# BUCK.net
KiCad netlist of a schematic drawn in Altium Designer
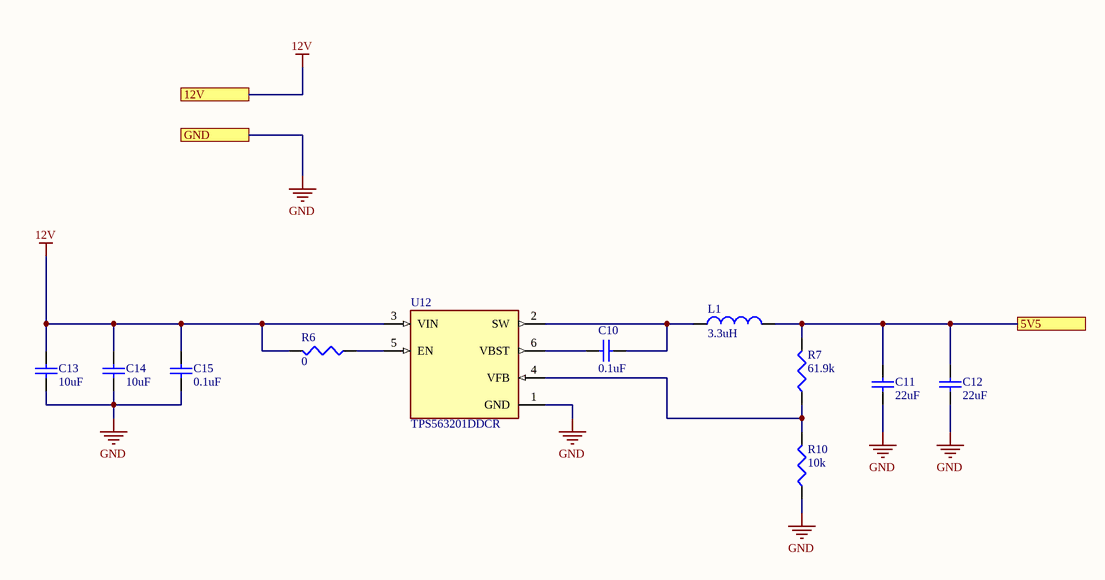
[diagram p0: BUCK.SchDoc]

(export (version "E")
  (design (tool "Eeschema 10.0.6"))
  (components
    (comp (ref "C10")
      (value "0.1uF")
      (footprint "SMD-0603")
      (description "Ceramic Capacitor 0603")
      (libsource (lib "LCR") (part "CAP0603"))
    )
    (comp (ref "C11")
      (value "22uF")
      (footprint "SMD-0805")
      (description "Ceramic Capacitor 0805 Imperial (2012 Metric)")
      (libsource (lib "LCR") (part "CAP0805"))
    )
    (comp (ref "C12")
      (value "22uF")
      (footprint "SMD-0805")
      (description "Ceramic Capacitor 0805 Imperial (2012 Metric)")
      (libsource (lib "LCR") (part "CAP0805"))
    )
    (comp (ref "C13")
      (value "10uF")
      (footprint "SMD-1206")
      (description "Ceramic Capacitor 1206 Imperial, 25V")
      (libsource (lib "LCR") (part "CAP1206_HV"))
    )
    (comp (ref "C14")
      (value "10uF")
      (footprint "SMD-1206")
      (description "Ceramic Capacitor 1206 Imperial, 25V")
      (libsource (lib "LCR") (part "CAP1206_HV"))
    )
    (comp (ref "C15")
      (value "0.1uF")
      (footprint "SMD-0603")
      (description "Ceramic Capacitor 0603, 25V")
      (libsource (lib "LCR") (part "CAP0603_HV"))
    )
    (comp (ref "L1")
      (value "3.3uH")
      (footprint "SMD-2525")
      (description "VLS6045EX type Inductor 2525")
      (libsource (lib "LCR") (part "VLS6045EX"))
    )
    (comp (ref "R6")
      (value "0")
      (footprint "SMD-0603")
      (description "Resistor-0603")
      (libsource (lib "LCR") (part "RES0603"))
    )
    (comp (ref "R7")
      (value "61.9k")
      (footprint "SMD-0603")
      (description "Resistor-0603")
      (libsource (lib "LCR") (part "RES0603"))
    )
    (comp (ref "R10")
      (value "10k")
      (footprint "SMD-0603")
      (description "Resistor-0603")
      (libsource (lib "LCR") (part "RES0603"))
    )
    (comp (ref "U12")
      (value "TPS563201DDCR")
      (footprint "SOT95P280X110-6N")
      (description "4.5 V to 17 V input, 3 A output, synchronous step-down converter in Eco-mode")
      (fields (field (name "MF") "Texas Instruments"))
      (libsource (lib "PowerManagement") (part "TPS563201DDCR"))
    )
  )
  (nets
    (net (code "1") (name "/5V5") (class "Default")
      (node (ref "C11") (pin "2") (pinfunction "2_2") (pintype "passive"))
      (node (ref "C12") (pin "2") (pinfunction "2_2") (pintype "passive"))
      (node (ref "L1") (pin "2") (pinfunction "2_2") (pintype "passive"))
      (node (ref "R7") (pin "2") (pinfunction "2_2") (pintype "passive"))
    )
    (net (code "2") (name "12V") (class "Default")
      (node (ref "C13") (pin "2") (pinfunction "2_2") (pintype "passive"))
      (node (ref "C14") (pin "2") (pinfunction "2_2") (pintype "passive"))
      (node (ref "C15") (pin "2") (pinfunction "2_2") (pintype "passive"))
      (node (ref "R6") (pin "2") (pinfunction "2_2") (pintype "passive"))
      (node (ref "U12") (pin "3") (pinfunction "VIN_3") (pintype "input"))
    )
    (net (code "3") (name "GND") (class "Default")
      (node (ref "C11") (pin "1") (pinfunction "1_1") (pintype "passive"))
      (node (ref "C12") (pin "1") (pinfunction "1_1") (pintype "passive"))
      (node (ref "C13") (pin "1") (pinfunction "1_1") (pintype "passive"))
      (node (ref "C14") (pin "1") (pinfunction "1_1") (pintype "passive"))
      (node (ref "C15") (pin "1") (pinfunction "1_1") (pintype "passive"))
      (node (ref "R10") (pin "1") (pinfunction "1_1") (pintype "passive"))
      (node (ref "U12") (pin "1") (pinfunction "GND_1") (pintype "power_in"))
    )
    (net (code "4") (name "Net-(U12-EN)") (class "Default")
      (node (ref "R6") (pin "1") (pinfunction "1_1") (pintype "passive"))
      (node (ref "U12") (pin "5") (pinfunction "EN_5") (pintype "input"))
    )
    (net (code "5") (name "Net-(U12-SW)") (class "Default")
      (node (ref "C10") (pin "2") (pinfunction "2_2") (pintype "passive"))
      (node (ref "L1") (pin "1") (pinfunction "1_1") (pintype "passive"))
      (node (ref "U12") (pin "2") (pinfunction "SW_2") (pintype "output"))
    )
    (net (code "6") (name "Net-(U12-VBST)") (class "Default")
      (node (ref "C10") (pin "1") (pinfunction "1_1") (pintype "passive"))
      (node (ref "U12") (pin "6") (pinfunction "VBST_6") (pintype "output"))
    )
    (net (code "7") (name "Net-(U12-VFB)") (class "Default")
      (node (ref "R10") (pin "2") (pinfunction "2_2") (pintype "passive"))
      (node (ref "R7") (pin "1") (pinfunction "1_1") (pintype "passive"))
      (node (ref "U12") (pin "4") (pinfunction "VFB_4") (pintype "input"))
    )
  )
)
